# SparkFun_Pulse_Oximeter_Heart-Rate_Senso.net
KiCad netlist of a schematic drawn in EAGLE
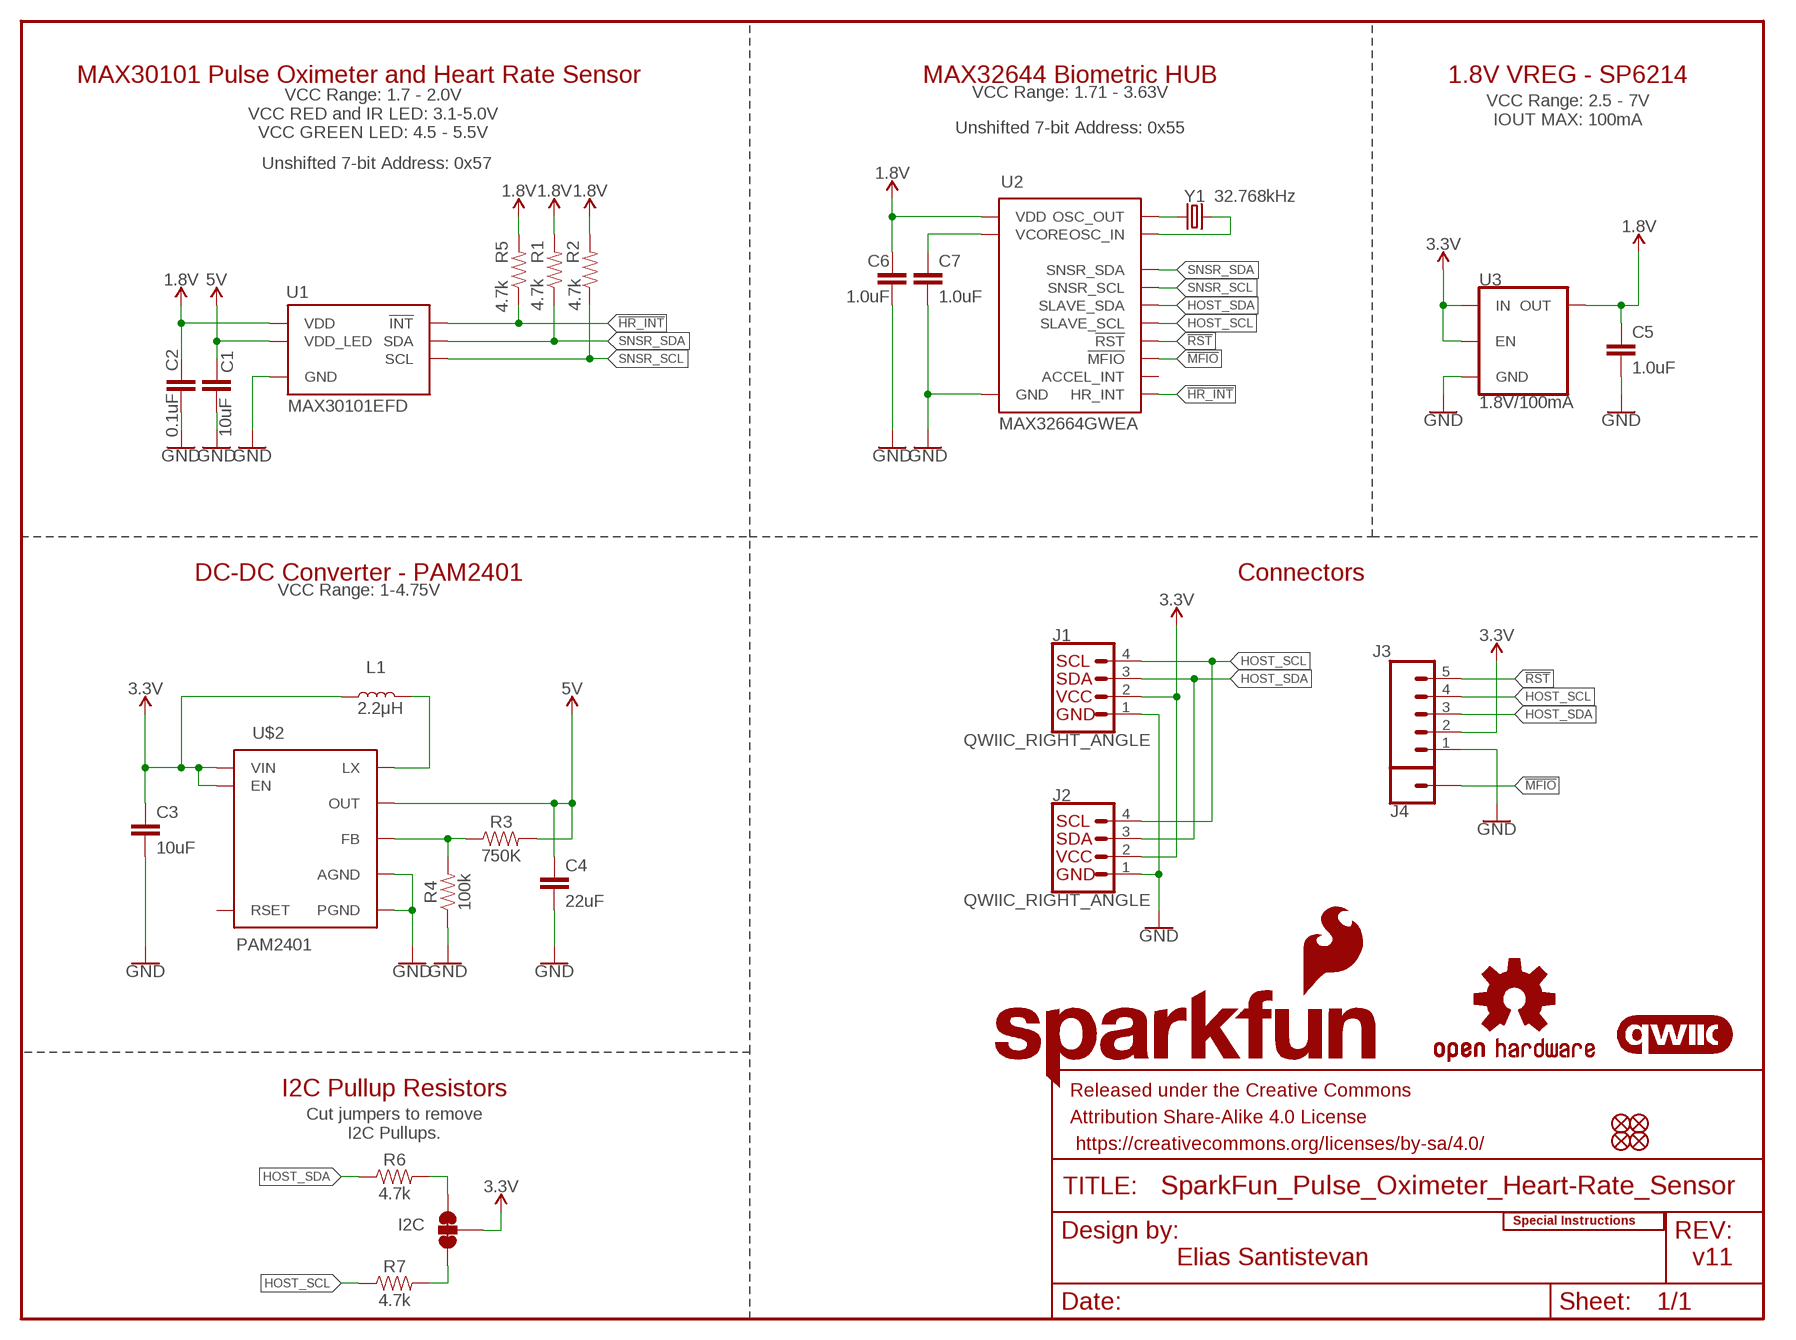
[diagram p0: schematic, sheet 1]

(export (version "E")
  (design (tool "Eeschema 10.0.6"))
  (components
    (comp (ref "C1")
      (value "10uF")
      (footprint "eagle-import:0603")
      (libsource (lib "eagle-import") (part "10UF-0603-6.3V-20%"))
    )
    (comp (ref "C2")
      (value "0.1uF")
      (footprint "eagle-import:0402-TIGHT")
      (libsource (lib "eagle-import") (part "0.1UF-0402T-16V-10%"))
    )
    (comp (ref "C3")
      (value "10uF")
      (footprint "eagle-import:0603")
      (libsource (lib "eagle-import") (part "10UF-0603-6.3V-20%"))
    )
    (comp (ref "C4")
      (value "22uF")
      (footprint "eagle-import:0805")
      (libsource (lib "eagle-import") (part "22UF-0805-6.3V-20%"))
    )
    (comp (ref "C5")
      (value "1.0uF")
      (footprint "eagle-import:0603")
      (libsource (lib "eagle-import") (part "1.0UF-0603-16V-10%"))
    )
    (comp (ref "C6")
      (value "1.0uF")
      (footprint "eagle-import:0402-TIGHT")
      (libsource (lib "eagle-import") (part "1.0UF-0402T-16V-10%"))
    )
    (comp (ref "C7")
      (value "1.0uF")
      (footprint "eagle-import:0402-TIGHT")
      (libsource (lib "eagle-import") (part "1.0UF-0402T-16V-10%"))
    )
    (comp (ref "FD1")
      (value "FIDUCIALUFIDUCIAL")
      (footprint "eagle-import:FIDUCIAL-MICRO")
      (libsource (lib "eagle-import") (part "FIDUCIALUFIDUCIAL"))
    )
    (comp (ref "FD2")
      (value "FIDUCIALUFIDUCIAL")
      (footprint "eagle-import:FIDUCIAL-MICRO")
      (libsource (lib "eagle-import") (part "FIDUCIALUFIDUCIAL"))
    )
    (comp (ref "FD3")
      (value "FIDUCIALUFIDUCIAL")
      (footprint "eagle-import:FIDUCIAL-MICRO")
      (libsource (lib "eagle-import") (part "FIDUCIALUFIDUCIAL"))
    )
    (comp (ref "FD4")
      (value "FIDUCIALUFIDUCIAL")
      (footprint "eagle-import:FIDUCIAL-MICRO")
      (libsource (lib "eagle-import") (part "FIDUCIALUFIDUCIAL"))
    )
    (comp (ref "FRAME1")
      (value "FRAME-LETTER")
      (footprint "eagle-import:CREATIVE_COMMONS")
      (libsource (lib "eagle-import") (part "FRAME-LETTER"))
    )
    (comp (ref "I2C")
      (value "JUMPER-SMT_3_2-NC_TRACE_SILK")
      (footprint "eagle-import:SMT-JUMPER_3_2-NC_TRACE_SILK")
      (libsource (lib "eagle-import") (part "JUMPER-SMT_3_2-NC_TRACE_SILK"))
    )
    (comp (ref "J1")
      (value "QWIIC_RIGHT_ANGLE")
      (footprint "eagle-import:JST04_1MM_RA")
      (libsource (lib "eagle-import") (part "QWIIC_CONNECTORJS-1MM"))
    )
    (comp (ref "J2")
      (value "QWIIC_RIGHT_ANGLE")
      (footprint "eagle-import:JST04_1MM_RA")
      (libsource (lib "eagle-import") (part "QWIIC_CONNECTORJS-1MM"))
    )
    (comp (ref "J3")
      (value "CONN_05NO_SILK")
      (footprint "eagle-import:1X05_NO_SILK")
      (libsource (lib "eagle-import") (part "CONN_05NO_SILK"))
    )
    (comp (ref "J4")
      (value "CONN_01PTH_NO_SILK_YES_STOP")
      (footprint "eagle-import:1X01_NO_SILK")
      (libsource (lib "eagle-import") (part "CONN_01PTH_NO_SILK_YES_STOP"))
    )
    (comp (ref "L1")
      (value "2.2μH")
      (footprint "eagle-import:0806")
      (libsource (lib "eagle-import") (part "2.2μH_SHIELDED_INDUCTOR"))
    )
    (comp (ref "LOGO1")
      (value "SFE_LOGO_FLAME.1_INCH")
      (footprint "eagle-import:SFE_LOGO_FLAME_.1")
      (libsource (lib "eagle-import") (part "SFE_LOGO_FLAME.1_INCH"))
    )
    (comp (ref "LOGO2")
      (value "OSHW-LOGOMINI")
      (footprint "eagle-import:OSHW-LOGO-MINI")
      (libsource (lib "eagle-import") (part "OSHW-LOGOMINI"))
    )
    (comp (ref "LOGO3")
      (value "SFE_LOGO_NAME.1_INCH")
      (footprint "eagle-import:SFE_LOGO_NAME_.1")
      (libsource (lib "eagle-import") (part "SFE_LOGO_NAME.1_INCH"))
    )
    (comp (ref "LOGO4")
      (value "SPECIAL_INSTRUCTIONS-ORDERING")
      (footprint "eagle-import:ORDERING_INSTRUCTIONS")
      (libsource (lib "eagle-import") (part "SPECIAL_INSTRUCTIONS-ORDERING"))
    )
    (comp (ref "LOGO5")
      (value "QWIIC_LOGO_4MM")
      (footprint "eagle-import:QWIIC_4MM")
      (libsource (lib "eagle-import") (part "QWIIC_LOGO_4MM"))
    )
    (comp (ref "R1")
      (value "4.7k")
      (footprint "eagle-import:0603")
      (libsource (lib "eagle-import") (part "4.7KOHM-0603-1/10W-1%"))
    )
    (comp (ref "R2")
      (value "4.7k")
      (footprint "eagle-import:0603")
      (libsource (lib "eagle-import") (part "4.7KOHM-0603-1/10W-1%"))
    )
    (comp (ref "R3")
      (value "750K")
      (footprint "eagle-import:0603")
      (libsource (lib "eagle-import") (part "750KOHM-0603-1/10W-1%"))
    )
    (comp (ref "R4")
      (value "100k")
      (footprint "eagle-import:0402-TIGHT")
      (libsource (lib "eagle-import") (part "100KOHM-0402T-1/16W-1%"))
    )
    (comp (ref "R5")
      (value "4.7k")
      (footprint "eagle-import:0603")
      (libsource (lib "eagle-import") (part "4.7KOHM-0603-1/10W-1%"))
    )
    (comp (ref "R6")
      (value "4.7k")
      (footprint "eagle-import:0603")
      (libsource (lib "eagle-import") (part "4.7KOHM-0603-1/10W-1%"))
    )
    (comp (ref "R7")
      (value "4.7k")
      (footprint "eagle-import:0603")
      (libsource (lib "eagle-import") (part "4.7KOHM-0603-1/10W-1%"))
    )
    (comp (ref "U$2")
      (value "PAM2401")
      (footprint "eagle-import:MSOP8")
      (libsource (lib "eagle-import") (part "PAM2401"))
    )
    (comp (ref "U1")
      (value "MAX30101EFD")
      (footprint "eagle-import:14_PIN_OESIP")
      (libsource (lib "eagle-import") (part "MAX30101EFD"))
    )
    (comp (ref "U2")
      (value "MAX32664GWEA")
      (footprint "eagle-import:16_PIN_WLP")
      (libsource (lib "eagle-import") (part "MAX32664GWEA"))
    )
    (comp (ref "U3")
      (value "1.8V/100mA")
      (footprint "eagle-import:SC70")
      (libsource (lib "eagle-import") (part "V_REG_SP6214-1.8V"))
    )
    (comp (ref "Y1")
      (value "32.768kHz")
      (footprint "eagle-import:CRYSTAL-SMD-3.2X1.5MM")
      (libsource (lib "eagle-import") (part "CRYSTAL-32.768KHZSMD-3.2X1.5"))
    )
  )
  (nets
    (net (code "1") (name "/~{HR_INT}") (class "Default")
      (node (ref "R5") (pin "1") (pinfunction "1_1") (pintype "passive"))
      (node (ref "U1") (pin "P13") (pinfunction "~{INT}_P13") (pintype "bidirectional"))
      (node (ref "U2") (pin "6") (pinfunction "HR_INT_6") (pintype "bidirectional"))
    )
    (net (code "2") (name "/~{MFIO}") (class "Default")
      (node (ref "J4") (pin "1") (pinfunction "1_1") (pintype "passive"))
      (node (ref "U2") (pin "16") (pinfunction "~{MFIO}_16") (pintype "bidirectional"))
    )
    (net (code "3") (name "/~{RST}") (class "Default")
      (node (ref "J3") (pin "5") (pinfunction "5_5") (pintype "passive"))
      (node (ref "U2") (pin "12") (pinfunction "~{RST}_12") (pintype "bidirectional"))
    )
    (net (code "4") (name "1.8V") (class "Default")
      (node (ref "C2") (pin "1") (pinfunction "1_1") (pintype "passive"))
      (node (ref "C5") (pin "1") (pinfunction "1_1") (pintype "passive"))
      (node (ref "C6") (pin "1") (pinfunction "1_1") (pintype "passive"))
      (node (ref "R1") (pin "2") (pinfunction "2_2") (pintype "passive"))
      (node (ref "R2") (pin "2") (pinfunction "2_2") (pintype "passive"))
      (node (ref "R5") (pin "2") (pinfunction "2_2") (pintype "passive"))
      (node (ref "U1") (pin "P11") (pinfunction "VDD_P11") (pintype "power_in"))
      (node (ref "U2") (pin "3") (pinfunction "VDD_3") (pintype "power_in"))
      (node (ref "U3") (pin "5") (pinfunction "OUT_5") (pintype "passive"))
    )
    (net (code "5") (name "3.3V") (class "Default")
      (node (ref "C3") (pin "1") (pinfunction "1_1") (pintype "passive"))
      (node (ref "I2C") (pin "2") (pinfunction "2_2") (pintype "passive"))
      (node (ref "J1") (pin "2") (pinfunction "2_2") (pintype "power_in"))
      (node (ref "J2") (pin "2") (pinfunction "2_2") (pintype "power_in"))
      (node (ref "J3") (pin "2") (pinfunction "2_2") (pintype "passive"))
      (node (ref "L1") (pin "1") (pinfunction "1_1") (pintype "passive"))
      (node (ref "U$2") (pin "2") (pinfunction "EN_2") (pintype "bidirectional"))
      (node (ref "U$2") (pin "3") (pinfunction "VIN_3") (pintype "bidirectional"))
      (node (ref "U3") (pin "1") (pinfunction "IN_1") (pintype "input"))
      (node (ref "U3") (pin "3") (pinfunction "EN_3") (pintype "input"))
    )
    (net (code "6") (name "5V") (class "Default")
      (node (ref "C1") (pin "1") (pinfunction "1_1") (pintype "passive"))
      (node (ref "C4") (pin "1") (pinfunction "1_1") (pintype "passive"))
      (node (ref "R3") (pin "2") (pinfunction "2_2") (pintype "passive"))
      (node (ref "U$2") (pin "7") (pinfunction "OUT_7") (pintype "bidirectional"))
      (node (ref "U1") (pin "P10") (pinfunction "VDD_LED_P10") (pintype "power_in"))
      (node (ref "U1") (pin "P9") (pinfunction "VDD_LED_P9") (pintype "power_in"))
    )
    (net (code "7") (name "GND") (class "Default")
      (node (ref "C1") (pin "2") (pinfunction "2_2") (pintype "passive"))
      (node (ref "C2") (pin "2") (pinfunction "2_2") (pintype "passive"))
      (node (ref "C3") (pin "2") (pinfunction "2_2") (pintype "passive"))
      (node (ref "C4") (pin "2") (pinfunction "2_2") (pintype "passive"))
      (node (ref "C5") (pin "2") (pinfunction "2_2") (pintype "passive"))
      (node (ref "C6") (pin "2") (pinfunction "2_2") (pintype "passive"))
      (node (ref "C7") (pin "2") (pinfunction "2_2") (pintype "passive"))
      (node (ref "J1") (pin "1") (pinfunction "1_1") (pintype "power_in"))
      (node (ref "J2") (pin "1") (pinfunction "1_1") (pintype "power_in"))
      (node (ref "J3") (pin "1") (pinfunction "1_1") (pintype "passive"))
      (node (ref "R4") (pin "1") (pinfunction "1_1") (pintype "passive"))
      (node (ref "U$2") (pin "4") (pinfunction "AGND_4") (pintype "bidirectional"))
      (node (ref "U$2") (pin "8") (pinfunction "PGND_8") (pintype "bidirectional"))
      (node (ref "U1") (pin "P12") (pinfunction "GND_P12") (pintype "power_in"))
      (node (ref "U1") (pin "P4") (pinfunction "GND_P4") (pintype "power_in"))
      (node (ref "U2") (pin "13") (pinfunction "GND_13") (pintype "power_in"))
      (node (ref "U3") (pin "2") (pinfunction "GND_2") (pintype "input"))
    )
    (net (code "8") (name "HOST_SCL") (class "Default")
      (node (ref "J1") (pin "4") (pinfunction "4_4") (pintype "passive"))
      (node (ref "J2") (pin "4") (pinfunction "4_4") (pintype "passive"))
      (node (ref "J3") (pin "4") (pinfunction "4_4") (pintype "passive"))
      (node (ref "R7") (pin "1") (pinfunction "1_1") (pintype "passive"))
      (node (ref "U2") (pin "10") (pinfunction "SLAVE_SCL_10") (pintype "bidirectional"))
    )
    (net (code "9") (name "HOST_SDA") (class "Default")
      (node (ref "J1") (pin "3") (pinfunction "3_3") (pintype "passive"))
      (node (ref "J2") (pin "3") (pinfunction "3_3") (pintype "passive"))
      (node (ref "J3") (pin "3") (pinfunction "3_3") (pintype "passive"))
      (node (ref "R6") (pin "1") (pinfunction "1_1") (pintype "passive"))
      (node (ref "U2") (pin "9") (pinfunction "SLAVE_SDA_9") (pintype "bidirectional"))
    )
    (net (code "10") (name "Net-(I2C-Pad1)") (class "Default")
      (node (ref "I2C") (pin "1") (pinfunction "1_1") (pintype "passive"))
      (node (ref "R7") (pin "2") (pinfunction "2_2") (pintype "passive"))
    )
    (net (code "11") (name "Net-(I2C-Pad3)") (class "Default")
      (node (ref "I2C") (pin "3") (pinfunction "3_3") (pintype "passive"))
      (node (ref "R6") (pin "2") (pinfunction "2_2") (pintype "passive"))
    )
    (net (code "12") (name "Net-(U$2-FB)") (class "Default")
      (node (ref "R3") (pin "1") (pinfunction "1_1") (pintype "passive"))
      (node (ref "R4") (pin "2") (pinfunction "2_2") (pintype "passive"))
      (node (ref "U$2") (pin "5") (pinfunction "FB_5") (pintype "bidirectional"))
    )
    (net (code "13") (name "Net-(U$2-LX)") (class "Default")
      (node (ref "L1") (pin "2") (pinfunction "2_2") (pintype "passive"))
      (node (ref "U$2") (pin "1") (pinfunction "LX_1") (pintype "bidirectional"))
    )
    (net (code "14") (name "Net-(U2-OSC_IN)") (class "Default")
      (node (ref "U2") (pin "2") (pinfunction "OSC_IN_2") (pintype "bidirectional"))
      (node (ref "Y1") (pin "P$2") (pinfunction "2_P$2") (pintype "passive"))
    )
    (net (code "15") (name "Net-(U2-OSC_OUT)") (class "Default")
      (node (ref "U2") (pin "1") (pinfunction "OSC_OUT_1") (pintype "bidirectional"))
      (node (ref "Y1") (pin "P$1") (pinfunction "1_P$1") (pintype "passive"))
    )
    (net (code "16") (name "Net-(U2-VCORE)") (class "Default")
      (node (ref "C7") (pin "1") (pinfunction "1_1") (pintype "passive"))
      (node (ref "U2") (pin "4") (pinfunction "VCORE_4") (pintype "power_in"))
    )
    (net (code "17") (name "SNSR_SCL") (class "Default")
      (node (ref "R2") (pin "1") (pinfunction "1_1") (pintype "passive"))
      (node (ref "U1") (pin "P2") (pinfunction "SCL_P2") (pintype "bidirectional"))
      (node (ref "U2") (pin "5") (pinfunction "SNSR_SCL_5") (pintype "bidirectional"))
    )
    (net (code "18") (name "SNSR_SDA") (class "Default")
      (node (ref "R1") (pin "1") (pinfunction "1_1") (pintype "passive"))
      (node (ref "U1") (pin "P3") (pinfunction "SDA_P3") (pintype "bidirectional"))
      (node (ref "U2") (pin "14") (pinfunction "SNSR_SDA_14") (pintype "bidirectional"))
    )
    (net (code "19") (name "unconnected-(U$2-RSET-Pad6)") (class "Default")
      (node (ref "U$2") (pin "6") (pinfunction "RSET_6") (pintype "bidirectional"))
    )
    (net (code "20") (name "unconnected-(U2-ACCEL_INT-Pad15)") (class "Default")
      (node (ref "U2") (pin "15") (pinfunction "ACCEL_INT_15") (pintype "bidirectional"))
    )
  )
)
